# Top.net
KiCad netlist of a schematic drawn in Altium Designer
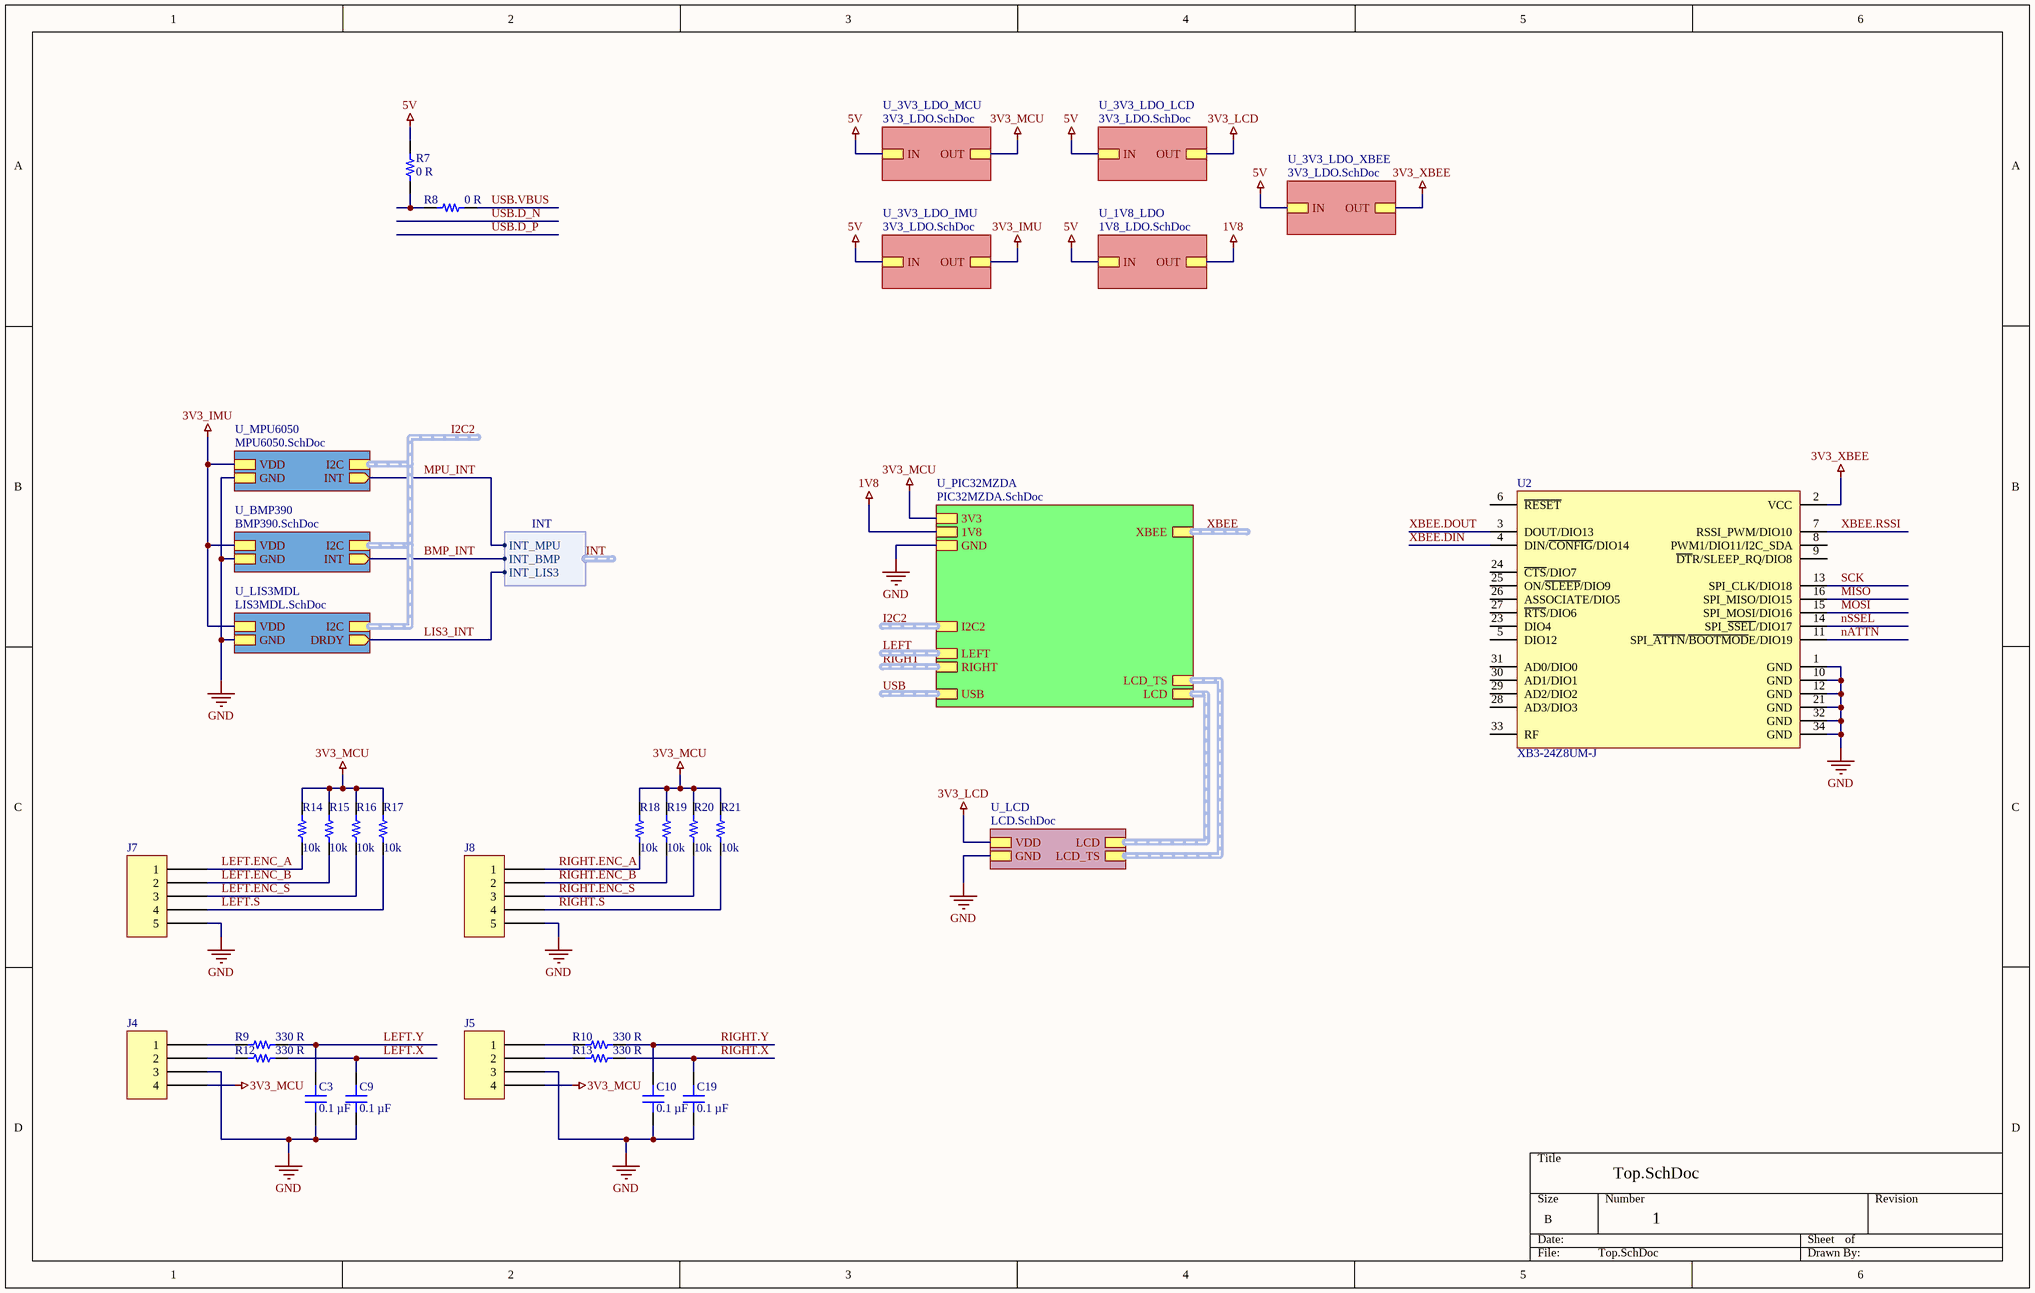
[diagram p0: Top.SchDoc]

(export (version "E")
  (design (tool "Eeschema 10.0.6"))
  (components
    (comp (ref "C3")
      (value "0.1 µF")
      (footprint "CAP 0402_1005")
      (description "CAP CER 0.1UF 16V X7R 0402")
      (fields (field (name "PART NUMBER") "C0402C104K4RACAUTO") (field (name "MANUFACTURER") "KEMET"))
      (libsource (lib "Celestial Altium Library - altium_library") (part "Capacitor"))
    )
    (comp (ref "C9")
      (value "0.1 µF")
      (footprint "CAP 0402_1005")
      (description "CAP CER 0.1UF 16V X7R 0402")
      (fields (field (name "PART NUMBER") "C0402C104K4RACAUTO") (field (name "MANUFACTURER") "KEMET"))
      (libsource (lib "Celestial Altium Library - altium_library") (part "Capacitor"))
    )
    (comp (ref "C10")
      (value "0.1 µF")
      (footprint "CAP 0402_1005")
      (description "CAP CER 0.1UF 16V X7R 0402")
      (fields (field (name "PART NUMBER") "C0402C104K4RACAUTO") (field (name "MANUFACTURER") "KEMET"))
      (libsource (lib "Celestial Altium Library - altium_library") (part "Capacitor"))
    )
    (comp (ref "C19")
      (value "0.1 µF")
      (footprint "CAP 0402_1005")
      (description "CAP CER 0.1UF 16V X7R 0402")
      (fields (field (name "PART NUMBER") "C0402C104K4RACAUTO") (field (name "MANUFACTURER") "KEMET"))
      (libsource (lib "Celestial Altium Library - altium_library") (part "Capacitor"))
    )
    (comp (ref "J4")
      (value "BM04B-SRSS-TB(LF)(SN)")
      (footprint "JST BM04B-SRSS-TB")
      (description "CONN HEADER SMD 4POS 1MM")
      (fields (field (name "MANUFACTURER") "JST Sales America Inc."))
      (libsource (lib "Celestial Altium Library - altium_library") (part "4 Pin"))
    )
    (comp (ref "J5")
      (value "BM04B-SRSS-TB(LF)(SN)")
      (footprint "JST BM04B-SRSS-TB")
      (description "CONN HEADER SMD 4POS 1MM")
      (fields (field (name "MANUFACTURER") "JST Sales America Inc."))
      (libsource (lib "Celestial Altium Library - altium_library") (part "4 Pin"))
    )
    (comp (ref "J7")
      (value "SM05B-SRSS-TB(LF)(SN)")
      (footprint "JST SM05B-SRSS-TB")
      (description "CONN HEADER SMD R/A 5POS 1MM")
      (fields (field (name "MANUFACTURER") "JST Sales America Inc."))
      (libsource (lib "Celestial Altium Library - altium_library") (part "5 Pin"))
    )
    (comp (ref "J8")
      (value "SM05B-SRSS-TB(LF)(SN)")
      (footprint "JST SM05B-SRSS-TB")
      (description "CONN HEADER SMD R/A 5POS 1MM")
      (fields (field (name "MANUFACTURER") "JST Sales America Inc."))
      (libsource (lib "Celestial Altium Library - altium_library") (part "5 Pin"))
    )
    (comp (ref "R7")
      (value "0 R")
      (footprint "RES 0603_1608")
      (description "RES 10K OHM 0.1% 1/16W 0603")
      (fields
        (field (name "PART NUMBER") "RNCS0603BKE10K0")
        (field (name "MANUFACTURER") "Stackpole Electronics Inc")
      )
      (libsource (lib "Celestial Altium Library - altium_library") (part "Resistor"))
    )
    (comp (ref "R8")
      (value "0 R")
      (footprint "RES 0402_1005")
      (description "RES 330 OHM 5% 1/16W 0402")
      (fields (field (name "PART NUMBER") "CRCW0402330RJNEDC") (field (name "MANUFACTURER") "Vishay Dale"))
      (libsource (lib "Celestial Altium Library - altium_library") (part "Resistor"))
    )
    (comp (ref "R9")
      (value "330 R")
      (footprint "RES 0402_1005")
      (description "RES 330 OHM 5% 1/16W 0402")
      (fields (field (name "PART NUMBER") "CRCW0402330RJNEDC") (field (name "MANUFACTURER") "Vishay Dale"))
      (libsource (lib "Celestial Altium Library - altium_library") (part "Resistor"))
    )
    (comp (ref "R10")
      (value "330 R")
      (footprint "RES 0402_1005")
      (description "RES 330 OHM 5% 1/16W 0402")
      (fields (field (name "PART NUMBER") "CRCW0402330RJNEDC") (field (name "MANUFACTURER") "Vishay Dale"))
      (libsource (lib "Celestial Altium Library - altium_library") (part "Resistor"))
    )
    (comp (ref "R12")
      (value "330 R")
      (footprint "RES 0402_1005")
      (description "RES 330 OHM 5% 1/16W 0402")
      (fields (field (name "PART NUMBER") "CRCW0402330RJNEDC") (field (name "MANUFACTURER") "Vishay Dale"))
      (libsource (lib "Celestial Altium Library - altium_library") (part "Resistor"))
    )
    (comp (ref "R13")
      (value "330 R")
      (footprint "RES 0402_1005")
      (description "RES 330 OHM 5% 1/16W 0402")
      (fields (field (name "PART NUMBER") "CRCW0402330RJNEDC") (field (name "MANUFACTURER") "Vishay Dale"))
      (libsource (lib "Celestial Altium Library - altium_library") (part "Resistor"))
    )
    (comp (ref "R14")
      (value "10k")
      (footprint "RES 0402_1005")
      (description "RES 330 OHM 5% 1/16W 0402")
      (fields (field (name "PART NUMBER") "CRCW0402330RJNEDC") (field (name "MANUFACTURER") "Vishay Dale"))
      (libsource (lib "Celestial Altium Library - altium_library") (part "Resistor"))
    )
    (comp (ref "R15")
      (value "10k")
      (footprint "RES 0402_1005")
      (description "RES 330 OHM 5% 1/16W 0402")
      (fields (field (name "PART NUMBER") "CRCW0402330RJNEDC") (field (name "MANUFACTURER") "Vishay Dale"))
      (libsource (lib "Celestial Altium Library - altium_library") (part "Resistor"))
    )
    (comp (ref "R16")
      (value "10k")
      (footprint "RES 0402_1005")
      (description "RES 330 OHM 5% 1/16W 0402")
      (fields (field (name "PART NUMBER") "CRCW0402330RJNEDC") (field (name "MANUFACTURER") "Vishay Dale"))
      (libsource (lib "Celestial Altium Library - altium_library") (part "Resistor"))
    )
    (comp (ref "R17")
      (value "10k")
      (footprint "RES 0402_1005")
      (description "RES 330 OHM 5% 1/16W 0402")
      (fields (field (name "PART NUMBER") "CRCW0402330RJNEDC") (field (name "MANUFACTURER") "Vishay Dale"))
      (libsource (lib "Celestial Altium Library - altium_library") (part "Resistor"))
    )
    (comp (ref "R18")
      (value "10k")
      (footprint "RES 0402_1005")
      (description "RES 330 OHM 5% 1/16W 0402")
      (fields (field (name "PART NUMBER") "CRCW0402330RJNEDC") (field (name "MANUFACTURER") "Vishay Dale"))
      (libsource (lib "Celestial Altium Library - altium_library") (part "Resistor"))
    )
    (comp (ref "R19")
      (value "10k")
      (footprint "RES 0402_1005")
      (description "RES 330 OHM 5% 1/16W 0402")
      (fields (field (name "PART NUMBER") "CRCW0402330RJNEDC") (field (name "MANUFACTURER") "Vishay Dale"))
      (libsource (lib "Celestial Altium Library - altium_library") (part "Resistor"))
    )
    (comp (ref "R20")
      (value "10k")
      (footprint "RES 0402_1005")
      (description "RES 330 OHM 5% 1/16W 0402")
      (fields (field (name "PART NUMBER") "CRCW0402330RJNEDC") (field (name "MANUFACTURER") "Vishay Dale"))
      (libsource (lib "Celestial Altium Library - altium_library") (part "Resistor"))
    )
    (comp (ref "R21")
      (value "10k")
      (footprint "RES 0402_1005")
      (description "RES 330 OHM 5% 1/16W 0402")
      (fields (field (name "PART NUMBER") "CRCW0402330RJNEDC") (field (name "MANUFACTURER") "Vishay Dale"))
      (libsource (lib "Celestial Altium Library - altium_library") (part "Resistor"))
    )
    (comp (ref "U2")
      (value "XB3-24Z8UM-J")
      (footprint "XCVR_XB3-24Z8UM-J")
      (description "802.15.4 Zigbee Transceiver Module 2.4GHz Antenna Not Included, U.FL Surface Mount")
      (fields (field (name "MF") "Digi International"))
      (libsource (lib "IC") (part "XB3-24Z8UM-J"))
    )
  )
  (nets
    (net (code "11") (name "/LEFT.ENC_A") (class "Default")
      (node (ref "J7") (pin "1") (pinfunction "1_1") (pintype "passive"))
      (node (ref "R14") (pin "2") (pinfunction "2_2") (pintype "passive"))
    )
    (net (code "12") (name "/LEFT.ENC_B") (class "Default")
      (node (ref "J7") (pin "2") (pinfunction "2_2") (pintype "passive"))
      (node (ref "R15") (pin "2") (pinfunction "2_2") (pintype "passive"))
    )
    (net (code "13") (name "/LEFT.ENC_S") (class "Default")
      (node (ref "J7") (pin "3") (pinfunction "3_3") (pintype "passive"))
      (node (ref "R16") (pin "2") (pinfunction "2_2") (pintype "passive"))
    )
    (net (code "14") (name "/LEFT.S") (class "Default")
      (node (ref "J7") (pin "4") (pinfunction "4_4") (pintype "passive"))
      (node (ref "R17") (pin "2") (pinfunction "2_2") (pintype "passive"))
    )
    (net (code "15") (name "/LEFT.X") (class "Default")
      (node (ref "C9") (pin "2") (pinfunction "2_2") (pintype "passive"))
      (node (ref "R12") (pin "1") (pinfunction "1_1") (pintype "passive"))
    )
    (net (code "16") (name "/LEFT.Y") (class "Default")
      (node (ref "C3") (pin "2") (pinfunction "2_2") (pintype "passive"))
      (node (ref "R9") (pin "1") (pinfunction "1_1") (pintype "passive"))
    )
    (net (code "18") (name "/MISO") (class "Default")
      (node (ref "U2") (pin "16") (pinfunction "SPI_MISO/DIO15_16") (pintype "passive"))
    )
    (net (code "19") (name "/MOSI") (class "Default")
      (node (ref "U2") (pin "15") (pinfunction "SPI_MOSI/DIO16_15") (pintype "passive"))
    )
    (net (code "21") (name "/RIGHT.ENC_A") (class "Default")
      (node (ref "J8") (pin "1") (pinfunction "1_1") (pintype "passive"))
      (node (ref "R18") (pin "2") (pinfunction "2_2") (pintype "passive"))
    )
    (net (code "22") (name "/RIGHT.ENC_B") (class "Default")
      (node (ref "J8") (pin "2") (pinfunction "2_2") (pintype "passive"))
      (node (ref "R19") (pin "2") (pinfunction "2_2") (pintype "passive"))
    )
    (net (code "23") (name "/RIGHT.ENC_S") (class "Default")
      (node (ref "J8") (pin "3") (pinfunction "3_3") (pintype "passive"))
      (node (ref "R20") (pin "2") (pinfunction "2_2") (pintype "passive"))
    )
    (net (code "24") (name "/RIGHT.S") (class "Default")
      (node (ref "J8") (pin "4") (pinfunction "4_4") (pintype "passive"))
      (node (ref "R21") (pin "2") (pinfunction "2_2") (pintype "passive"))
    )
    (net (code "25") (name "/RIGHT.X") (class "Default")
      (node (ref "C19") (pin "2") (pinfunction "2_2") (pintype "passive"))
      (node (ref "R13") (pin "1") (pinfunction "1_1") (pintype "passive"))
    )
    (net (code "26") (name "/RIGHT.Y") (class "Default")
      (node (ref "C10") (pin "2") (pinfunction "2_2") (pintype "passive"))
      (node (ref "R10") (pin "1") (pinfunction "1_1") (pintype "passive"))
    )
    (net (code "27") (name "/SCK") (class "Default")
      (node (ref "U2") (pin "13") (pinfunction "SPI_CLK/DIO18_13") (pintype "passive"))
    )
    (net (code "30") (name "/USB.VBUS") (class "Default")
      (node (ref "R8") (pin "1") (pinfunction "1_1") (pintype "passive"))
    )
    (net (code "31") (name "/XBEE.DIN") (class "Default")
      (node (ref "U2") (pin "4") (pinfunction "DIN/~{CONFIG}/DIO14_4") (pintype "passive"))
    )
    (net (code "32") (name "/XBEE.DOUT") (class "Default")
      (node (ref "U2") (pin "3") (pinfunction "DOUT/DIO13_3") (pintype "passive"))
    )
    (net (code "33") (name "/XBEE.RSSI") (class "Default")
      (node (ref "U2") (pin "7") (pinfunction "RSSI_PWM/DIO10_7") (pintype "passive"))
    )
    (net (code "34") (name "/nATTN") (class "Default")
      (node (ref "U2") (pin "11") (pinfunction "SPI_~{ATTN}/~{BOOTMOD}E/DIO19_11") (pintype "passive"))
    )
    (net (code "35") (name "/nSSEL") (class "Default")
      (node (ref "U2") (pin "14") (pinfunction "SPI_~{SSEL}/DIO17_14") (pintype "passive"))
    )
    (net (code "44") (name "3V3_MCU") (class "Default")
      (node (ref "J4") (pin "4") (pinfunction "4_4") (pintype "passive"))
      (node (ref "J5") (pin "4") (pinfunction "4_4") (pintype "passive"))
      (node (ref "R14") (pin "1") (pinfunction "1_1") (pintype "passive"))
      (node (ref "R15") (pin "1") (pinfunction "1_1") (pintype "passive"))
      (node (ref "R16") (pin "1") (pinfunction "1_1") (pintype "passive"))
      (node (ref "R17") (pin "1") (pinfunction "1_1") (pintype "passive"))
      (node (ref "R18") (pin "1") (pinfunction "1_1") (pintype "passive"))
      (node (ref "R19") (pin "1") (pinfunction "1_1") (pintype "passive"))
      (node (ref "R20") (pin "1") (pinfunction "1_1") (pintype "passive"))
      (node (ref "R21") (pin "1") (pinfunction "1_1") (pintype "passive"))
    )
    (net (code "45") (name "3V3_XBEE") (class "Default")
      (node (ref "U2") (pin "2") (pinfunction "VCC_2") (pintype "power_in"))
    )
    (net (code "46") (name "5V") (class "Default")
      (node (ref "R7") (pin "2") (pinfunction "2_2") (pintype "passive"))
    )
    (net (code "47") (name "GND") (class "Default")
      (node (ref "C10") (pin "1") (pinfunction "1_1") (pintype "passive"))
      (node (ref "C19") (pin "1") (pinfunction "1_1") (pintype "passive"))
      (node (ref "C3") (pin "1") (pinfunction "1_1") (pintype "passive"))
      (node (ref "C9") (pin "1") (pinfunction "1_1") (pintype "passive"))
      (node (ref "J4") (pin "3") (pinfunction "3_3") (pintype "passive"))
      (node (ref "J5") (pin "3") (pinfunction "3_3") (pintype "passive"))
      (node (ref "J7") (pin "5") (pinfunction "5_5") (pintype "passive"))
      (node (ref "J8") (pin "5") (pinfunction "5_5") (pintype "passive"))
      (node (ref "U2") (pin "1") (pinfunction "GND_1") (pintype "power_in"))
      (node (ref "U2") (pin "10") (pinfunction "GND_10") (pintype "power_in"))
      (node (ref "U2") (pin "12") (pinfunction "GND_12") (pintype "power_in"))
      (node (ref "U2") (pin "21") (pinfunction "GND_21") (pintype "power_in"))
      (node (ref "U2") (pin "32") (pinfunction "GND_32") (pintype "power_in"))
      (node (ref "U2") (pin "34") (pinfunction "GND_34") (pintype "power_in"))
    )
    (net (code "48") (name "Net-(J4-Pad1)") (class "Default")
      (node (ref "J4") (pin "1") (pinfunction "1_1") (pintype "passive"))
      (node (ref "R9") (pin "2") (pinfunction "2_2") (pintype "passive"))
    )
    (net (code "49") (name "Net-(J4-Pad2)") (class "Default")
      (node (ref "J4") (pin "2") (pinfunction "2_2") (pintype "passive"))
      (node (ref "R12") (pin "2") (pinfunction "2_2") (pintype "passive"))
    )
    (net (code "50") (name "Net-(J5-Pad1)") (class "Default")
      (node (ref "J5") (pin "1") (pinfunction "1_1") (pintype "passive"))
      (node (ref "R10") (pin "2") (pinfunction "2_2") (pintype "passive"))
    )
    (net (code "51") (name "Net-(J5-Pad2)") (class "Default")
      (node (ref "J5") (pin "2") (pinfunction "2_2") (pintype "passive"))
      (node (ref "R13") (pin "2") (pinfunction "2_2") (pintype "passive"))
    )
    (net (code "52") (name "Net-(R7-Pad1)") (class "Default")
      (node (ref "R7") (pin "1") (pinfunction "1_1") (pintype "passive"))
      (node (ref "R8") (pin "2") (pinfunction "2_2") (pintype "passive"))
    )
    (net (code "53") (name "unconnected-(U2-AD0{slash}DIO0-Pad31)") (class "Default")
      (node (ref "U2") (pin "31") (pinfunction "AD0/DIO0_31") (pintype "passive"))
    )
    (net (code "54") (name "unconnected-(U2-AD1{slash}DIO1-Pad30)") (class "Default")
      (node (ref "U2") (pin "30") (pinfunction "AD1/DIO1_30") (pintype "passive"))
    )
    (net (code "55") (name "unconnected-(U2-AD2{slash}DIO2-Pad29)") (class "Default")
      (node (ref "U2") (pin "29") (pinfunction "AD2/DIO2_29") (pintype "passive"))
    )
    (net (code "56") (name "unconnected-(U2-AD3{slash}DIO3-Pad28)") (class "Default")
      (node (ref "U2") (pin "28") (pinfunction "AD3/DIO3_28") (pintype "passive"))
    )
    (net (code "57") (name "unconnected-(U2-ASSOCIATE{slash}DIO5-Pad26)") (class "Default")
      (node (ref "U2") (pin "26") (pinfunction "ASSOCIATE/DIO5_26") (pintype "passive"))
    )
    (net (code "58") (name "unconnected-(U2-DIO4-Pad23)") (class "Default")
      (node (ref "U2") (pin "23") (pinfunction "DIO4_23") (pintype "passive"))
    )
    (net (code "59") (name "unconnected-(U2-DIO12-Pad5)") (class "Default")
      (node (ref "U2") (pin "5") (pinfunction "DIO12_5") (pintype "passive"))
    )
    (net (code "60") (name "unconnected-(U2-ON{slash}~{SLEEP}{slash}DIO9-Pad25)") (class "Default")
      (node (ref "U2") (pin "25") (pinfunction "ON/~{SLEEP}/DIO9_25") (pintype "passive"))
    )
    (net (code "61") (name "unconnected-(U2-PWM1{slash}DIO11{slash}I2C_SDA-Pad8)") (class "Default")
      (node (ref "U2") (pin "8") (pinfunction "PWM1/DIO11/I2C_SDA_8") (pintype "passive"))
    )
    (net (code "62") (name "unconnected-(U2-RF-Pad33)") (class "Default")
      (node (ref "U2") (pin "33") (pinfunction "RF_33") (pintype "passive"))
    )
    (net (code "63") (name "unconnected-(U2-~{CTS}{slash}DIO7-Pad24)") (class "Default")
      (node (ref "U2") (pin "24") (pinfunction "~{CTS}/DIO7_24") (pintype "passive"))
    )
    (net (code "64") (name "unconnected-(U2-~{DT}R{slash}SLEEP_RQ{slash}DIO8-Pad9)") (class "Default")
      (node (ref "U2") (pin "9") (pinfunction "~{DT}R/SLEEP_RQ/DIO8_9") (pintype "passive"))
    )
    (net (code "65") (name "unconnected-(U2-~{RESET}-Pad6)") (class "Default")
      (node (ref "U2") (pin "6") (pinfunction "~{RESET}_6") (pintype "passive"))
    )
    (net (code "66") (name "unconnected-(U2-~{RTS}{slash}DIO6-Pad27)") (class "Default")
      (node (ref "U2") (pin "27") (pinfunction "~{RTS}/DIO6_27") (pintype "passive"))
    )
  )
)
